# voltaged.net
KiCad netlist of a schematic drawn in EAGLE
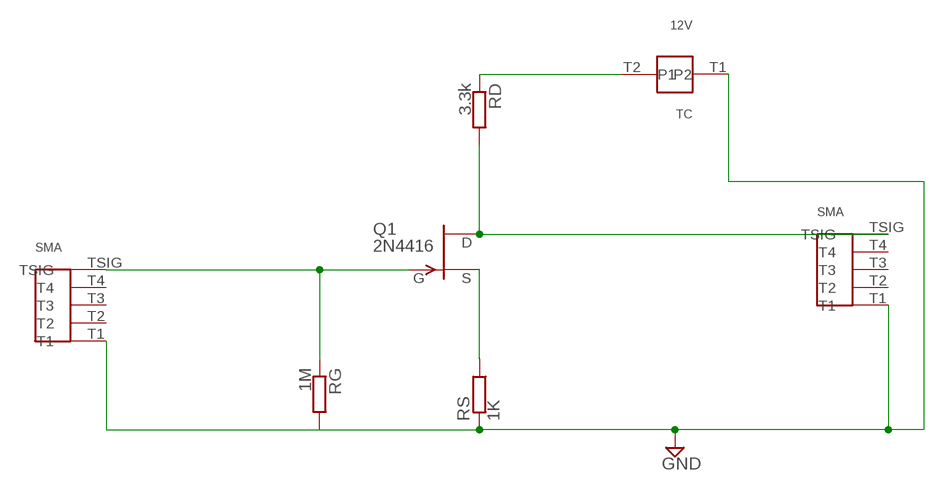
[diagram p0: schematic, sheet 1]

(export (version "E")
  (design (tool "Eeschema 10.0.6"))
  (components
    (comp (ref "Q1")
      (value "2N4416")
      (footprint "eagle-import:TO72")
      (libsource (lib "eagle-import") (part "2N4416"))
    )
    (comp (ref "RD")
      (value "3.3k")
      (footprint "eagle-import:SMR-0")
      (libsource (lib "eagle-import") (part "SMR-0"))
    )
    (comp (ref "RG")
      (value "1M")
      (footprint "eagle-import:SMR-0")
      (libsource (lib "eagle-import") (part "SMR-0"))
    )
    (comp (ref "RS")
      (value "1K")
      (footprint "eagle-import:SMR-0")
      (libsource (lib "eagle-import") (part "SMR-0"))
    )
    (comp (ref "U$1") (value "TC") (footprint "eagle-import:TC") (libsource (lib "eagle-import") (part "TC")))
    (comp (ref "U$2")
      (value "TC")
      (footprint "eagle-import:TC")
      (libsource (lib "eagle-import") (part "project2_TC"))
    )
    (comp (ref "U$3")
      (value "TC")
      (footprint "eagle-import:TC")
      (libsource (lib "eagle-import") (part "project2_TC"))
    )
  )
  (nets
    (net (code "1") (name "GND") (class "Default")
      (node (ref "RG") (pin "1") (pinfunction "1_1") (pintype "passive"))
      (node (ref "RS") (pin "2") (pinfunction "2_2") (pintype "passive"))
      (node (ref "U$1") (pin "T1") (pinfunction "P1_T1") (pintype "bidirectional"))
      (node (ref "U$2") (pin "T1") (pinfunction "T1_T1") (pintype "bidirectional"))
      (node (ref "U$3") (pin "T1") (pinfunction "T1_T1") (pintype "bidirectional"))
    )
    (net (code "2") (name "Net-(Q1-D)") (class "Default")
      (node (ref "Q1") (pin "2") (pinfunction "D_2") (pintype "passive"))
      (node (ref "RD") (pin "1") (pinfunction "1_1") (pintype "passive"))
      (node (ref "U$3") (pin "TSIG") (pinfunction "TSIG_TSIG") (pintype "bidirectional"))
    )
    (net (code "3") (name "Net-(Q1-G)") (class "Default")
      (node (ref "Q1") (pin "3") (pinfunction "G_3") (pintype "passive"))
      (node (ref "RG") (pin "2") (pinfunction "2_2") (pintype "passive"))
      (node (ref "U$2") (pin "TSIG") (pinfunction "TSIG_TSIG") (pintype "bidirectional"))
    )
    (net (code "4") (name "Net-(Q1-S)") (class "Default")
      (node (ref "Q1") (pin "1") (pinfunction "S_1") (pintype "passive"))
      (node (ref "RS") (pin "1") (pinfunction "1_1") (pintype "passive"))
    )
    (net (code "5") (name "Net-(U$1-P2)") (class "Default")
      (node (ref "RD") (pin "2") (pinfunction "2_2") (pintype "passive"))
      (node (ref "U$1") (pin "T2") (pinfunction "P2_T2") (pintype "bidirectional"))
    )
    (net (code "6") (name "unconnected-(U$2-PadT2)") (class "Default")
      (node (ref "U$2") (pin "T2") (pinfunction "T2_T2") (pintype "bidirectional"))
    )
    (net (code "7") (name "unconnected-(U$2-PadT3)") (class "Default")
      (node (ref "U$2") (pin "T3") (pinfunction "T3_T3") (pintype "bidirectional"))
    )
    (net (code "8") (name "unconnected-(U$2-PadT4)") (class "Default")
      (node (ref "U$2") (pin "T4") (pinfunction "T4_T4") (pintype "bidirectional"))
    )
    (net (code "9") (name "unconnected-(U$3-PadT2)") (class "Default")
      (node (ref "U$3") (pin "T2") (pinfunction "T2_T2") (pintype "bidirectional"))
    )
    (net (code "10") (name "unconnected-(U$3-PadT3)") (class "Default")
      (node (ref "U$3") (pin "T3") (pinfunction "T3_T3") (pintype "bidirectional"))
    )
    (net (code "11") (name "unconnected-(U$3-PadT4)") (class "Default")
      (node (ref "U$3") (pin "T4") (pinfunction "T4_T4") (pintype "bidirectional"))
    )
  )
)
